# gemschematic_Chris_edits.net
KiCad netlist of a schematic drawn in EAGLE
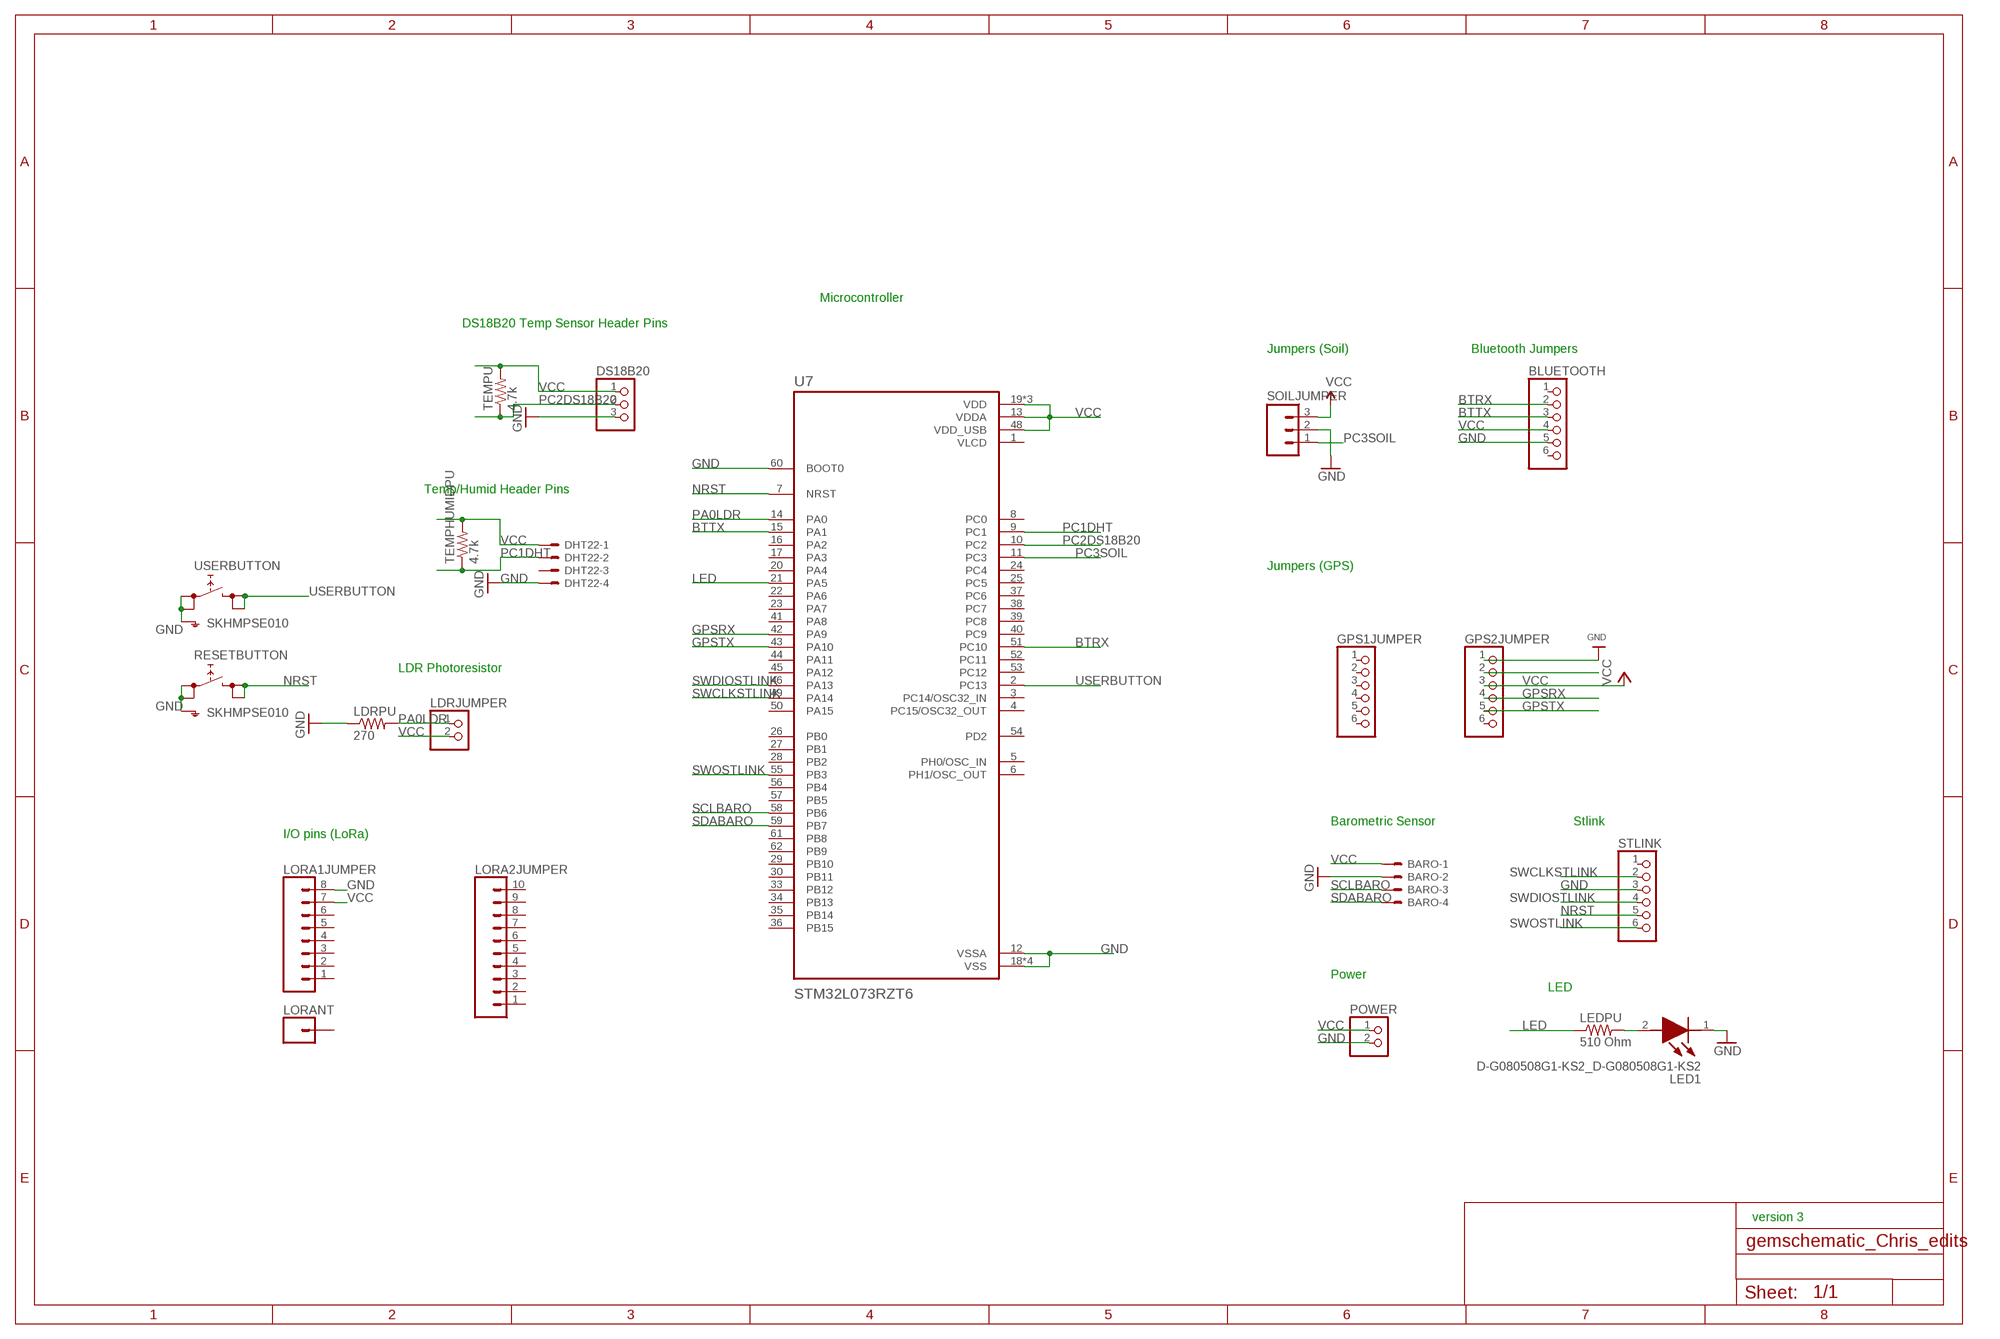
[diagram p0: schematic, sheet 1]

(export (version "E")
  (design (tool "Eeschema 10.0.6"))
  (components
    (comp (ref "BARO")
      (value "22-23-2041")
      (footprint "eagle-import:22-23-2041")
      (fields (field (name "MF") "MOLEX"))
      (libsource (lib "eagle-import") (part "22-23-2041"))
    )
    (comp (ref "BLUETOOTH")
      (value "PINHD-1X6")
      (footprint "eagle-import:1X06")
      (libsource (lib "eagle-import") (part "PINHD-1X6"))
    )
    (comp (ref "DHT22")
      (value "22-23-2041")
      (footprint "eagle-import:22-23-2041")
      (fields (field (name "MF") "MOLEX"))
      (libsource (lib "eagle-import") (part "22-23-2041"))
    )
    (comp (ref "DS18B20")
      (value "PINHD-1X3")
      (footprint "eagle-import:1X03")
      (libsource (lib "eagle-import") (part "PINHD-1X3"))
    )
    (comp (ref "GPS1JUMPER")
      (value "HEADER-1X670MIL")
      (footprint "eagle-import:1X06_ROUND_70")
      (libsource (lib "eagle-import") (part "HEADER-1X670MIL"))
    )
    (comp (ref "GPS2JUMPER")
      (value "HEADER-1X670MIL")
      (footprint "eagle-import:1X06_ROUND_70")
      (libsource (lib "eagle-import") (part "HEADER-1X670MIL"))
    )
    (comp (ref "LDRJUMPER")
      (value "PINHD-1X2")
      (footprint "eagle-import:1X02")
      (libsource (lib "eagle-import") (part "PINHD-1X2"))
    )
    (comp (ref "LDRPU")
      (value "270")
      (footprint "eagle-import:M0805")
      (libsource (lib "eagle-import") (part "R-US_M0805"))
    )
    (comp (ref "LED1")
      (value "D-G080508G1-KS2_D-G080508G1-KS2")
      (footprint "eagle-import:D-G080508G1-KS2_LEDC2012X85N")
      (fields (field (name "MANUFACTURER_PART_NUMBER") "D-G080508G1-KS2"))
      (libsource (lib "eagle-import") (part "D-G080508G1-KS2_D-G080508G1-KS2"))
    )
    (comp (ref "LEDPU")
      (value "510 Ohm")
      (footprint "eagle-import:M0805")
      (libsource (lib "eagle-import") (part "R-US_M0805"))
    )
    (comp (ref "LORA1JUMPER")
      (value "CONN_08NO_SILK_FEMALE_PTH")
      (footprint "eagle-import:1X08_NO_SILK")
      (libsource (lib "eagle-import") (part "CONN_08NO_SILK_FEMALE_PTH"))
    )
    (comp (ref "LORA2JUMPER")
      (value "CONN_10NO_SILK_PTH_FEMALE")
      (footprint "eagle-import:1X10_NO_SILK")
      (libsource (lib "eagle-import") (part "CONN_10NO_SILK_PTH_FEMALE"))
    )
    (comp (ref "LORANT")
      (value "CONN_01PTH_NO_SILK_YES_STOP")
      (footprint "eagle-import:1X01_NO_SILK")
      (libsource (lib "eagle-import") (part "CONN_01PTH_NO_SILK_YES_STOP"))
    )
    (comp (ref "POWER")
      (value "PINHD-1X2")
      (footprint "eagle-import:1X02")
      (libsource (lib "eagle-import") (part "PINHD-1X2"))
    )
    (comp (ref "RESETBUTTON")
      (value "SKHMPSE010")
      (footprint "eagle-import:SKHMPXE010")
      (libsource (lib "eagle-import") (part "SKHMPE010S"))
    )
    (comp (ref "SOILJUMPER")
      (value "M03SCREW_LOCK")
      (footprint "eagle-import:SCREWTERMINAL-3.5MM-3_LOCK.007S")
      (libsource (lib "eagle-import") (part "M03SCREW_LOCK"))
    )
    (comp (ref "STLINK")
      (value "PINHD-1X6")
      (footprint "eagle-import:1X06")
      (libsource (lib "eagle-import") (part "PINHD-1X6"))
    )
    (comp (ref "TEMPHUMIDPU")
      (value "4.7k")
      (footprint "eagle-import:M0805")
      (libsource (lib "eagle-import") (part "R-US_M0805"))
    )
    (comp (ref "TEMPU")
      (value "4.7k")
      (footprint "eagle-import:M0805")
      (libsource (lib "eagle-import") (part "R-US_M0805"))
    )
    (comp (ref "U7")
      (value "STM32L073RZT6")
      (footprint "eagle-import:QFP50P1200X1200X160-64N")
      (fields (field (name "MF") "STMicroelectronics"))
      (libsource (lib "eagle-import") (part "STM32L073RZT6"))
    )
    (comp (ref "USERBUTTON")
      (value "SKHMPSE010")
      (footprint "eagle-import:SKHMPXE010")
      (libsource (lib "eagle-import") (part "SKHMPE010S"))
    )
  )
  (nets
    (net (code "1") (name "/BTRX") (class "Default")
      (node (ref "BLUETOOTH") (pin "2") (pinfunction "2_2") (pintype "passive"))
      (node (ref "U7") (pin "51") (pinfunction "PC10_51") (pintype "bidirectional"))
    )
    (net (code "2") (name "/BTTX") (class "Default")
      (node (ref "BLUETOOTH") (pin "3") (pinfunction "3_3") (pintype "passive"))
      (node (ref "U7") (pin "15") (pinfunction "PA1_15") (pintype "bidirectional"))
    )
    (net (code "3") (name "/GPSRX") (class "Default")
      (node (ref "GPS2JUMPER") (pin "4") (pinfunction "4_4") (pintype "passive"))
      (node (ref "U7") (pin "42") (pinfunction "PA9_42") (pintype "bidirectional"))
    )
    (net (code "4") (name "/GPSTX") (class "Default")
      (node (ref "GPS2JUMPER") (pin "5") (pinfunction "5_5") (pintype "passive"))
      (node (ref "U7") (pin "43") (pinfunction "PA10_43") (pintype "bidirectional"))
    )
    (net (code "5") (name "/LED") (class "Default")
      (node (ref "LEDPU") (pin "1") (pinfunction "1_1") (pintype "passive"))
      (node (ref "U7") (pin "21") (pinfunction "PA5_21") (pintype "bidirectional"))
    )
    (net (code "6") (name "/NRST") (class "Default")
      (node (ref "RESETBUTTON") (pin "3") (pinfunction "2.1_3") (pintype "passive"))
      (node (ref "RESETBUTTON") (pin "4") (pinfunction "2.2_4") (pintype "passive"))
      (node (ref "STLINK") (pin "5") (pinfunction "5_5") (pintype "passive"))
      (node (ref "U7") (pin "7") (pinfunction "NRST_7") (pintype "bidirectional"))
    )
    (net (code "7") (name "/PA0LDR") (class "Default")
      (node (ref "LDRJUMPER") (pin "1") (pinfunction "1_1") (pintype "passive"))
      (node (ref "LDRPU") (pin "2") (pinfunction "2_2") (pintype "passive"))
      (node (ref "U7") (pin "14") (pinfunction "PA0_14") (pintype "bidirectional"))
    )
    (net (code "8") (name "/PC1DHT") (class "Default")
      (node (ref "DHT22") (pin "2") (pinfunction "S_2") (pintype "passive"))
      (node (ref "TEMPHUMIDPU") (pin "1") (pinfunction "1_1") (pintype "passive"))
      (node (ref "U7") (pin "9") (pinfunction "PC1_9") (pintype "bidirectional"))
    )
    (net (code "9") (name "/PC2DS18B20") (class "Default")
      (node (ref "DS18B20") (pin "2") (pinfunction "2_2") (pintype "passive"))
      (node (ref "TEMPU") (pin "1") (pinfunction "1_1") (pintype "passive"))
      (node (ref "U7") (pin "10") (pinfunction "PC2_10") (pintype "bidirectional"))
    )
    (net (code "10") (name "/PC3SOIL") (class "Default")
      (node (ref "SOILJUMPER") (pin "1") (pinfunction "1_1") (pintype "passive"))
      (node (ref "U7") (pin "11") (pinfunction "PC3_11") (pintype "bidirectional"))
    )
    (net (code "11") (name "/SCLBARO") (class "Default")
      (node (ref "BARO") (pin "3") (pinfunction "S_3") (pintype "passive"))
      (node (ref "U7") (pin "58") (pinfunction "PB6_58") (pintype "bidirectional"))
    )
    (net (code "12") (name "/SDABARO") (class "Default")
      (node (ref "BARO") (pin "4") (pinfunction "S_4") (pintype "passive"))
      (node (ref "U7") (pin "59") (pinfunction "PB7_59") (pintype "bidirectional"))
    )
    (net (code "13") (name "/SWCLKSTLINK") (class "Default")
      (node (ref "STLINK") (pin "2") (pinfunction "2_2") (pintype "passive"))
      (node (ref "U7") (pin "49") (pinfunction "PA14_49") (pintype "bidirectional"))
    )
    (net (code "14") (name "/SWDIOSTLINK") (class "Default")
      (node (ref "STLINK") (pin "4") (pinfunction "4_4") (pintype "passive"))
      (node (ref "U7") (pin "46") (pinfunction "PA13_46") (pintype "bidirectional"))
    )
    (net (code "15") (name "/SWOSTLINK") (class "Default")
      (node (ref "STLINK") (pin "6") (pinfunction "6_6") (pintype "passive"))
      (node (ref "U7") (pin "55") (pinfunction "PB3_55") (pintype "bidirectional"))
    )
    (net (code "16") (name "/USERBUTTON") (class "Default")
      (node (ref "U7") (pin "2") (pinfunction "PC13_2") (pintype "bidirectional"))
      (node (ref "USERBUTTON") (pin "3") (pinfunction "2.1_3") (pintype "passive"))
      (node (ref "USERBUTTON") (pin "4") (pinfunction "2.2_4") (pintype "passive"))
    )
    (net (code "17") (name "/VLCD") (class "Default")
      (node (ref "U7") (pin "1") (pinfunction "VLCD_1") (pintype "power_in"))
    )
    (net (code "18") (name "GND") (class "Default")
      (node (ref "BARO") (pin "2") (pinfunction "S_2") (pintype "passive"))
      (node (ref "BLUETOOTH") (pin "5") (pinfunction "5_5") (pintype "passive"))
      (node (ref "DHT22") (pin "4") (pinfunction "S_4") (pintype "passive"))
      (node (ref "DS18B20") (pin "3") (pinfunction "3_3") (pintype "passive"))
      (node (ref "GPS2JUMPER") (pin "1") (pinfunction "1_1") (pintype "passive"))
      (node (ref "LDRPU") (pin "1") (pinfunction "1_1") (pintype "passive"))
      (node (ref "LED1") (pin "1") (pinfunction "K_1") (pintype "bidirectional"))
      (node (ref "LORA1JUMPER") (pin "8") (pinfunction "8_8") (pintype "passive"))
      (node (ref "POWER") (pin "2") (pinfunction "2_2") (pintype "passive"))
      (node (ref "RESETBUTTON") (pin "1") (pinfunction "1.1_1") (pintype "passive"))
      (node (ref "RESETBUTTON") (pin "2") (pinfunction "1.2_2") (pintype "passive"))
      (node (ref "RESETBUTTON") (pin "5") (pinfunction "SH_5") (pintype "passive"))
      (node (ref "SOILJUMPER") (pin "2") (pinfunction "2_2") (pintype "passive"))
      (node (ref "STLINK") (pin "3") (pinfunction "3_3") (pintype "passive"))
      (node (ref "U7") (pin "12") (pinfunction "VSSA_12") (pintype "power_in"))
      (node (ref "U7") (pin "18") (pinfunction "VSS_18") (pintype "power_in"))
      (node (ref "U7") (pin "31") (pinfunction "VSS_31") (pintype "power_in"))
      (node (ref "U7") (pin "47") (pinfunction "VSS_47") (pintype "power_in"))
      (node (ref "U7") (pin "60") (pinfunction "BOOT0_60") (pintype "input"))
      (node (ref "U7") (pin "63") (pinfunction "VSS_63") (pintype "power_in"))
      (node (ref "USERBUTTON") (pin "1") (pinfunction "1.1_1") (pintype "passive"))
      (node (ref "USERBUTTON") (pin "2") (pinfunction "1.2_2") (pintype "passive"))
      (node (ref "USERBUTTON") (pin "5") (pinfunction "SH_5") (pintype "passive"))
    )
    (net (code "19") (name "Net-(LED1-A)") (class "Default")
      (node (ref "LED1") (pin "2") (pinfunction "A_2") (pintype "bidirectional"))
      (node (ref "LEDPU") (pin "2") (pinfunction "2_2") (pintype "passive"))
    )
    (net (code "20") (name "VCC") (class "Default")
      (node (ref "BARO") (pin "1") (pinfunction "S_1") (pintype "passive"))
      (node (ref "BLUETOOTH") (pin "4") (pinfunction "4_4") (pintype "passive"))
      (node (ref "DHT22") (pin "1") (pinfunction "S_1") (pintype "passive"))
      (node (ref "DS18B20") (pin "1") (pinfunction "1_1") (pintype "passive"))
      (node (ref "GPS2JUMPER") (pin "3") (pinfunction "3_3") (pintype "passive"))
      (node (ref "LDRJUMPER") (pin "2") (pinfunction "2_2") (pintype "passive"))
      (node (ref "LORA1JUMPER") (pin "7") (pinfunction "7_7") (pintype "passive"))
      (node (ref "POWER") (pin "1") (pinfunction "1_1") (pintype "passive"))
      (node (ref "SOILJUMPER") (pin "3") (pinfunction "3_3") (pintype "passive"))
      (node (ref "TEMPHUMIDPU") (pin "2") (pinfunction "2_2") (pintype "passive"))
      (node (ref "TEMPU") (pin "2") (pinfunction "2_2") (pintype "passive"))
      (node (ref "U7") (pin "13") (pinfunction "VDDA_13") (pintype "power_in"))
      (node (ref "U7") (pin "19") (pinfunction "VDD_19") (pintype "power_in"))
      (node (ref "U7") (pin "32") (pinfunction "VDD_32") (pintype "power_in"))
      (node (ref "U7") (pin "48") (pinfunction "VDD_USB_48") (pintype "power_in"))
      (node (ref "U7") (pin "64") (pinfunction "VDD_64") (pintype "power_in"))
    )
    (net (code "21") (name "unconnected-(BLUETOOTH-Pad1)") (class "Default")
      (node (ref "BLUETOOTH") (pin "1") (pinfunction "1_1") (pintype "passive"))
    )
    (net (code "22") (name "unconnected-(BLUETOOTH-Pad6)") (class "Default")
      (node (ref "BLUETOOTH") (pin "6") (pinfunction "6_6") (pintype "passive"))
    )
    (net (code "23") (name "unconnected-(DHT22C-S-Pad3)") (class "Default")
      (node (ref "DHT22") (pin "3") (pinfunction "S_3") (pintype "passive"))
    )
    (net (code "24") (name "unconnected-(GPS1JUMPER-Pad1)") (class "Default")
      (node (ref "GPS1JUMPER") (pin "1") (pinfunction "1_1") (pintype "passive"))
    )
    (net (code "25") (name "unconnected-(GPS1JUMPER-Pad2)") (class "Default")
      (node (ref "GPS1JUMPER") (pin "2") (pinfunction "2_2") (pintype "passive"))
    )
    (net (code "26") (name "unconnected-(GPS1JUMPER-Pad3)") (class "Default")
      (node (ref "GPS1JUMPER") (pin "3") (pinfunction "3_3") (pintype "passive"))
    )
    (net (code "27") (name "unconnected-(GPS1JUMPER-Pad4)") (class "Default")
      (node (ref "GPS1JUMPER") (pin "4") (pinfunction "4_4") (pintype "passive"))
    )
    (net (code "28") (name "unconnected-(GPS1JUMPER-Pad5)") (class "Default")
      (node (ref "GPS1JUMPER") (pin "5") (pinfunction "5_5") (pintype "passive"))
    )
    (net (code "29") (name "unconnected-(GPS1JUMPER-Pad6)") (class "Default")
      (node (ref "GPS1JUMPER") (pin "6") (pinfunction "6_6") (pintype "passive"))
    )
    (net (code "30") (name "unconnected-(GPS2JUMPER-Pad2)") (class "Default")
      (node (ref "GPS2JUMPER") (pin "2") (pinfunction "2_2") (pintype "passive"))
    )
    (net (code "31") (name "unconnected-(GPS2JUMPER-Pad6)") (class "Default")
      (node (ref "GPS2JUMPER") (pin "6") (pinfunction "6_6") (pintype "passive"))
    )
    (net (code "32") (name "unconnected-(LORA1JUMPER-Pad1)") (class "Default")
      (node (ref "LORA1JUMPER") (pin "1") (pinfunction "1_1") (pintype "passive"))
    )
    (net (code "33") (name "unconnected-(LORA1JUMPER-Pad2)") (class "Default")
      (node (ref "LORA1JUMPER") (pin "2") (pinfunction "2_2") (pintype "passive"))
    )
    (net (code "34") (name "unconnected-(LORA1JUMPER-Pad3)") (class "Default")
      (node (ref "LORA1JUMPER") (pin "3") (pinfunction "3_3") (pintype "passive"))
    )
    (net (code "35") (name "unconnected-(LORA1JUMPER-Pad4)") (class "Default")
      (node (ref "LORA1JUMPER") (pin "4") (pinfunction "4_4") (pintype "passive"))
    )
    (net (code "36") (name "unconnected-(LORA1JUMPER-Pad5)") (class "Default")
      (node (ref "LORA1JUMPER") (pin "5") (pinfunction "5_5") (pintype "passive"))
    )
    (net (code "37") (name "unconnected-(LORA1JUMPER-Pad6)") (class "Default")
      (node (ref "LORA1JUMPER") (pin "6") (pinfunction "6_6") (pintype "passive"))
    )
    (net (code "38") (name "unconnected-(LORA2JUMPER-Pad1)") (class "Default")
      (node (ref "LORA2JUMPER") (pin "1") (pinfunction "1_1") (pintype "passive"))
    )
    (net (code "39") (name "unconnected-(LORA2JUMPER-Pad2)") (class "Default")
      (node (ref "LORA2JUMPER") (pin "2") (pinfunction "2_2") (pintype "passive"))
    )
    (net (code "40") (name "unconnected-(LORA2JUMPER-Pad3)") (class "Default")
      (node (ref "LORA2JUMPER") (pin "3") (pinfunction "3_3") (pintype "passive"))
    )
    (net (code "41") (name "unconnected-(LORA2JUMPER-Pad4)") (class "Default")
      (node (ref "LORA2JUMPER") (pin "4") (pinfunction "4_4") (pintype "passive"))
    )
    (net (code "42") (name "unconnected-(LORA2JUMPER-Pad5)") (class "Default")
      (node (ref "LORA2JUMPER") (pin "5") (pinfunction "5_5") (pintype "passive"))
    )
    (net (code "43") (name "unconnected-(LORA2JUMPER-Pad6)") (class "Default")
      (node (ref "LORA2JUMPER") (pin "6") (pinfunction "6_6") (pintype "passive"))
    )
    (net (code "44") (name "unconnected-(LORA2JUMPER-Pad7)") (class "Default")
      (node (ref "LORA2JUMPER") (pin "7") (pinfunction "7_7") (pintype "passive"))
    )
    (net (code "45") (name "unconnected-(LORA2JUMPER-Pad8)") (class "Default")
      (node (ref "LORA2JUMPER") (pin "8") (pinfunction "8_8") (pintype "passive"))
    )
    (net (code "46") (name "unconnected-(LORA2JUMPER-Pad9)") (class "Default")
      (node (ref "LORA2JUMPER") (pin "9") (pinfunction "9_9") (pintype "passive"))
    )
    (net (code "47") (name "unconnected-(LORA2JUMPER-Pad10)") (class "Default")
      (node (ref "LORA2JUMPER") (pin "10") (pinfunction "10_10") (pintype "passive"))
    )
    (net (code "48") (name "unconnected-(LORANT-Pad1)") (class "Default")
      (node (ref "LORANT") (pin "1") (pinfunction "1_1") (pintype "passive"))
    )
    (net (code "49") (name "unconnected-(STLINK-Pad1)") (class "Default")
      (node (ref "STLINK") (pin "1") (pinfunction "1_1") (pintype "passive"))
    )
    (net (code "50") (name "unconnected-(U7-PA2-Pad16)") (class "Default")
      (node (ref "U7") (pin "16") (pinfunction "PA2_16") (pintype "bidirectional"))
    )
    (net (code "51") (name "unconnected-(U7-PA3-Pad17)") (class "Default")
      (node (ref "U7") (pin "17") (pinfunction "PA3_17") (pintype "bidirectional"))
    )
    (net (code "52") (name "unconnected-(U7-PA4-Pad20)") (class "Default")
      (node (ref "U7") (pin "20") (pinfunction "PA4_20") (pintype "bidirectional"))
    )
    (net (code "53") (name "unconnected-(U7-PA6-Pad22)") (class "Default")
      (node (ref "U7") (pin "22") (pinfunction "PA6_22") (pintype "bidirectional"))
    )
    (net (code "54") (name "unconnected-(U7-PA7-Pad23)") (class "Default")
      (node (ref "U7") (pin "23") (pinfunction "PA7_23") (pintype "bidirectional"))
    )
    (net (code "55") (name "unconnected-(U7-PA8-Pad41)") (class "Default")
      (node (ref "U7") (pin "41") (pinfunction "PA8_41") (pintype "bidirectional"))
    )
    (net (code "56") (name "unconnected-(U7-PA11-Pad44)") (class "Default")
      (node (ref "U7") (pin "44") (pinfunction "PA11_44") (pintype "bidirectional"))
    )
    (net (code "57") (name "unconnected-(U7-PA12-Pad45)") (class "Default")
      (node (ref "U7") (pin "45") (pinfunction "PA12_45") (pintype "bidirectional"))
    )
    (net (code "58") (name "unconnected-(U7-PA15-Pad50)") (class "Default")
      (node (ref "U7") (pin "50") (pinfunction "PA15_50") (pintype "bidirectional"))
    )
    (net (code "59") (name "unconnected-(U7-PB0-Pad26)") (class "Default")
      (node (ref "U7") (pin "26") (pinfunction "PB0_26") (pintype "bidirectional"))
    )
    (net (code "60") (name "unconnected-(U7-PB1-Pad27)") (class "Default")
      (node (ref "U7") (pin "27") (pinfunction "PB1_27") (pintype "bidirectional"))
    )
    (net (code "61") (name "unconnected-(U7-PB2-Pad28)") (class "Default")
      (node (ref "U7") (pin "28") (pinfunction "PB2_28") (pintype "bidirectional"))
    )
    (net (code "62") (name "unconnected-(U7-PB4-Pad56)") (class "Default")
      (node (ref "U7") (pin "56") (pinfunction "PB4_56") (pintype "bidirectional"))
    )
    (net (code "63") (name "unconnected-(U7-PB5-Pad57)") (class "Default")
      (node (ref "U7") (pin "57") (pinfunction "PB5_57") (pintype "bidirectional"))
    )
    (net (code "64") (name "unconnected-(U7-PB8-Pad61)") (class "Default")
      (node (ref "U7") (pin "61") (pinfunction "PB8_61") (pintype "bidirectional"))
    )
    (net (code "65") (name "unconnected-(U7-PB9-Pad62)") (class "Default")
      (node (ref "U7") (pin "62") (pinfunction "PB9_62") (pintype "bidirectional"))
    )
    (net (code "66") (name "unconnected-(U7-PB10-Pad29)") (class "Default")
      (node (ref "U7") (pin "29") (pinfunction "PB10_29") (pintype "bidirectional"))
    )
    (net (code "67") (name "unconnected-(U7-PB11-Pad30)") (class "Default")
      (node (ref "U7") (pin "30") (pinfunction "PB11_30") (pintype "bidirectional"))
    )
    (net (code "68") (name "unconnected-(U7-PB12-Pad33)") (class "Default")
      (node (ref "U7") (pin "33") (pinfunction "PB12_33") (pintype "bidirectional"))
    )
    (net (code "69") (name "unconnected-(U7-PB13-Pad34)") (class "Default")
      (node (ref "U7") (pin "34") (pinfunction "PB13_34") (pintype "bidirectional"))
    )
    (net (code "70") (name "unconnected-(U7-PB14-Pad35)") (class "Default")
      (node (ref "U7") (pin "35") (pinfunction "PB14_35") (pintype "bidirectional"))
    )
    (net (code "71") (name "unconnected-(U7-PB15-Pad36)") (class "Default")
      (node (ref "U7") (pin "36") (pinfunction "PB15_36") (pintype "bidirectional"))
    )
    (net (code "72") (name "unconnected-(U7-PC0-Pad8)") (class "Default")
      (node (ref "U7") (pin "8") (pinfunction "PC0_8") (pintype "bidirectional"))
    )
    (net (code "73") (name "unconnected-(U7-PC4-Pad24)") (class "Default")
      (node (ref "U7") (pin "24") (pinfunction "PC4_24") (pintype "bidirectional"))
    )
    (net (code "74") (name "unconnected-(U7-PC5-Pad25)") (class "Default")
      (node (ref "U7") (pin "25") (pinfunction "PC5_25") (pintype "bidirectional"))
    )
    (net (code "75") (name "unconnected-(U7-PC6-Pad37)") (class "Default")
      (node (ref "U7") (pin "37") (pinfunction "PC6_37") (pintype "bidirectional"))
    )
    (net (code "76") (name "unconnected-(U7-PC7-Pad38)") (class "Default")
      (node (ref "U7") (pin "38") (pinfunction "PC7_38") (pintype "bidirectional"))
    )
    (net (code "77") (name "unconnected-(U7-PC8-Pad39)") (class "Default")
      (node (ref "U7") (pin "39") (pinfunction "PC8_39") (pintype "bidirectional"))
    )
    (net (code "78") (name "unconnected-(U7-PC9-Pad40)") (class "Default")
      (node (ref "U7") (pin "40") (pinfunction "PC9_40") (pintype "bidirectional"))
    )
    (net (code "79") (name "unconnected-(U7-PC11-Pad52)") (class "Default")
      (node (ref "U7") (pin "52") (pinfunction "PC11_52") (pintype "bidirectional"))
    )
    (net (code "80") (name "unconnected-(U7-PC12-Pad53)") (class "Default")
      (node (ref "U7") (pin "53") (pinfunction "PC12_53") (pintype "bidirectional"))
    )
    (net (code "81") (name "unconnected-(U7-PC14{slash}OSC32_IN-Pad3)") (class "Default")
      (node (ref "U7") (pin "3") (pinfunction "PC14/OSC32_IN_3") (pintype "bidirectional"))
    )
    (net (code "82") (name "unconnected-(U7-PC15{slash}OSC32_OUT-Pad4)") (class "Default")
      (node (ref "U7") (pin "4") (pinfunction "PC15/OSC32_OUT_4") (pintype "bidirectional"))
    )
    (net (code "83") (name "unconnected-(U7-PD2-Pad54)") (class "Default")
      (node (ref "U7") (pin "54") (pinfunction "PD2_54") (pintype "bidirectional"))
    )
    (net (code "84") (name "unconnected-(U7-PH0{slash}OSC_IN-Pad5)") (class "Default")
      (node (ref "U7") (pin "5") (pinfunction "PH0/OSC_IN_5") (pintype "bidirectional"))
    )
    (net (code "85") (name "unconnected-(U7-PH1{slash}OSC_OUT-Pad6)") (class "Default")
      (node (ref "U7") (pin "6") (pinfunction "PH1/OSC_OUT_6") (pintype "bidirectional"))
    )
  )
)
